# Gastroscopy-Controller_Relay.net
KiCad netlist of a schematic drawn in Altium Designer
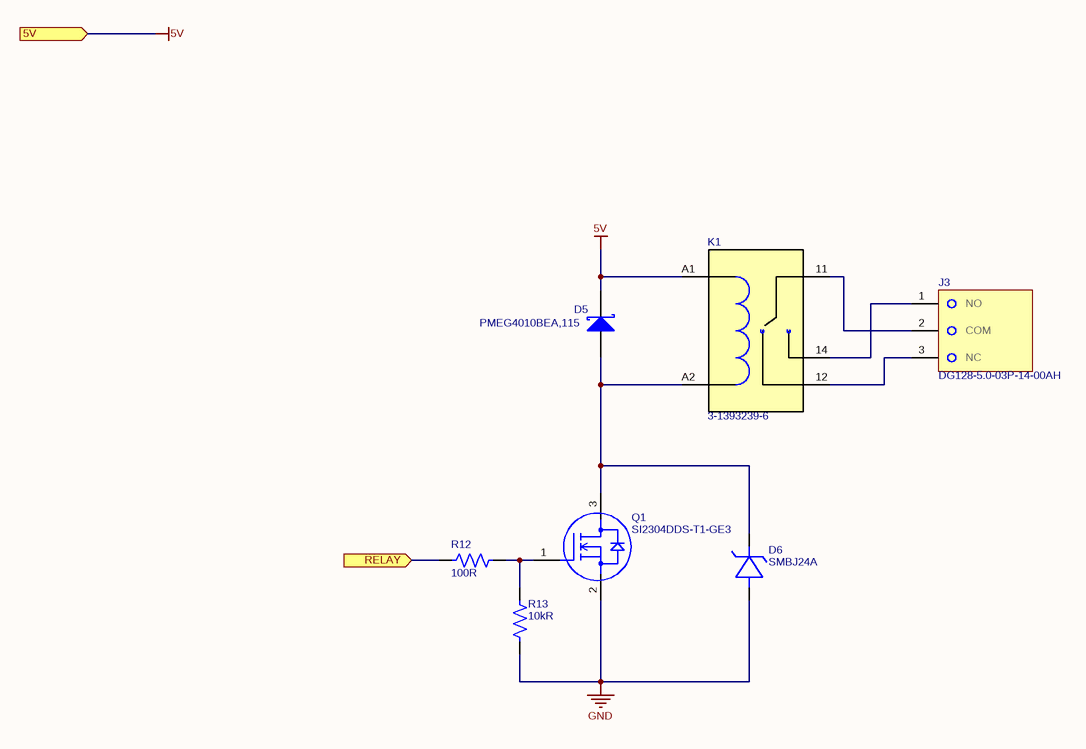
[diagram p0: Gastroscopy-Controller_Relay.SchDoc]

(export (version "E")
  (design (tool "Eeschema 10.0.6"))
  (components
    (comp (ref "D5")
      (value "PMEG4010BEA,115")
      (footprint "SOD-323")
      (description "DIODE SCHOTTKY 40V 1A SOD323")
      (fields (field (name "MANUFACTURER") "Nexperia"))
      (libsource (lib "Gastroscopy-Controller") (part "PMEG4010BEA,115"))
    )
    (comp (ref "D6")
      (value "SMBJ24A")
      (footprint "SMB")
      (description "TVS DIODE 24VWM 38.9VC SMB")
      (libsource (lib "Gastroscopy-Controller") (part "SMBJ24A"))
    )
    (comp (ref "J3")
      (value "DG128-5.0-03P-14-00AH")
      (footprint "DG128-5.0-03P-14")
      (description "TERM BLK 3P TOP ENTRY 5MM SMD")
      (libsource (lib "Industrial-Controller") (part "DG128-5.0-03P-14"))
    )
    (comp (ref "K1")
      (value "3-1393239-6")
      (footprint "3-1393239-6")
      (description "RELAY GEN PURPOSE SPDT 10A 5V")
      (libsource (lib "Gastroscopy-Controller") (part "3-1393239-6"))
    )
    (comp (ref "Q1")
      (value "SI2304DDS-T1-GE3")
      (footprint "SOT-23-3")
      (description "MOSFET N-CH 30V 3.3A/3.6A SOT23")
      (libsource (lib "Gastroscopy-Controller") (part "SI2304DDS-T1-GE3"))
    )
    (comp (ref "R12")
      (value "100R")
      (footprint "RES_0603")
      (description "RES 100 OHM 1% 1/10W 0603")
      (fields (field (name "TOLERANCE") "1%"))
      (libsource (lib "Gastroscopy-Controller") (part "RC0603FR-07100RL"))
    )
    (comp (ref "R13")
      (value "10kR")
      (footprint "RES_0603")
      (description "RES 10K OHM 1% 1/10W 0603")
      (fields (field (name "TOLERANCE") "1%"))
      (libsource (lib "Gastroscopy-Controller") (part "RC0603FR-0710KL"))
    )
  )
  (nets
    (net (code "1") (name "/RELAY") (class "Default")
      (node (ref "R12") (pin "1") (pinfunction "1_1") (pintype "passive"))
    )
    (net (code "2") (name "5V") (class "Default")
      (node (ref "D5") (pin "1") (pinfunction "K_1") (pintype "passive"))
      (node (ref "K1") (pin "A1") (pinfunction "A1_A1") (pintype "passive"))
    )
    (net (code "3") (name "GND") (class "Default")
      (node (ref "D6") (pin "2") (pinfunction "A_2") (pintype "passive"))
      (node (ref "Q1") (pin "2") (pinfunction "S_2") (pintype "passive"))
      (node (ref "R13") (pin "2") (pinfunction "2_2") (pintype "passive"))
    )
    (net (code "4") (name "Net-(D5-A)") (class "Default")
      (node (ref "D5") (pin "2") (pinfunction "A_2") (pintype "passive"))
      (node (ref "D6") (pin "1") (pinfunction "C_1") (pintype "passive"))
      (node (ref "K1") (pin "A2") (pinfunction "A2_A2") (pintype "passive"))
      (node (ref "Q1") (pin "3") (pinfunction "D_3") (pintype "passive"))
    )
    (net (code "5") (name "Net-(K1-COM)") (class "Default")
      (node (ref "J3") (pin "2") (pinfunction "2_2") (pintype "passive"))
      (node (ref "K1") (pin "11") (pinfunction "COM_11") (pintype "passive"))
    )
    (net (code "6") (name "Net-(K1-NC)") (class "Default")
      (node (ref "J3") (pin "3") (pinfunction "3_3") (pintype "passive"))
      (node (ref "K1") (pin "12") (pinfunction "NC_12") (pintype "passive"))
    )
    (net (code "7") (name "Net-(K1-NO)") (class "Default")
      (node (ref "J3") (pin "1") (pinfunction "1_1") (pintype "passive"))
      (node (ref "K1") (pin "14") (pinfunction "NO_14") (pintype "passive"))
    )
    (net (code "8") (name "Net-(Q1-G)") (class "Default")
      (node (ref "Q1") (pin "1") (pinfunction "G_1") (pintype "passive"))
      (node (ref "R12") (pin "2") (pinfunction "2_2") (pintype "passive"))
      (node (ref "R13") (pin "1") (pinfunction "1_1") (pintype "passive"))
    )
  )
)
